# untitled_-.net
KiCad netlist of a schematic drawn in EAGLE
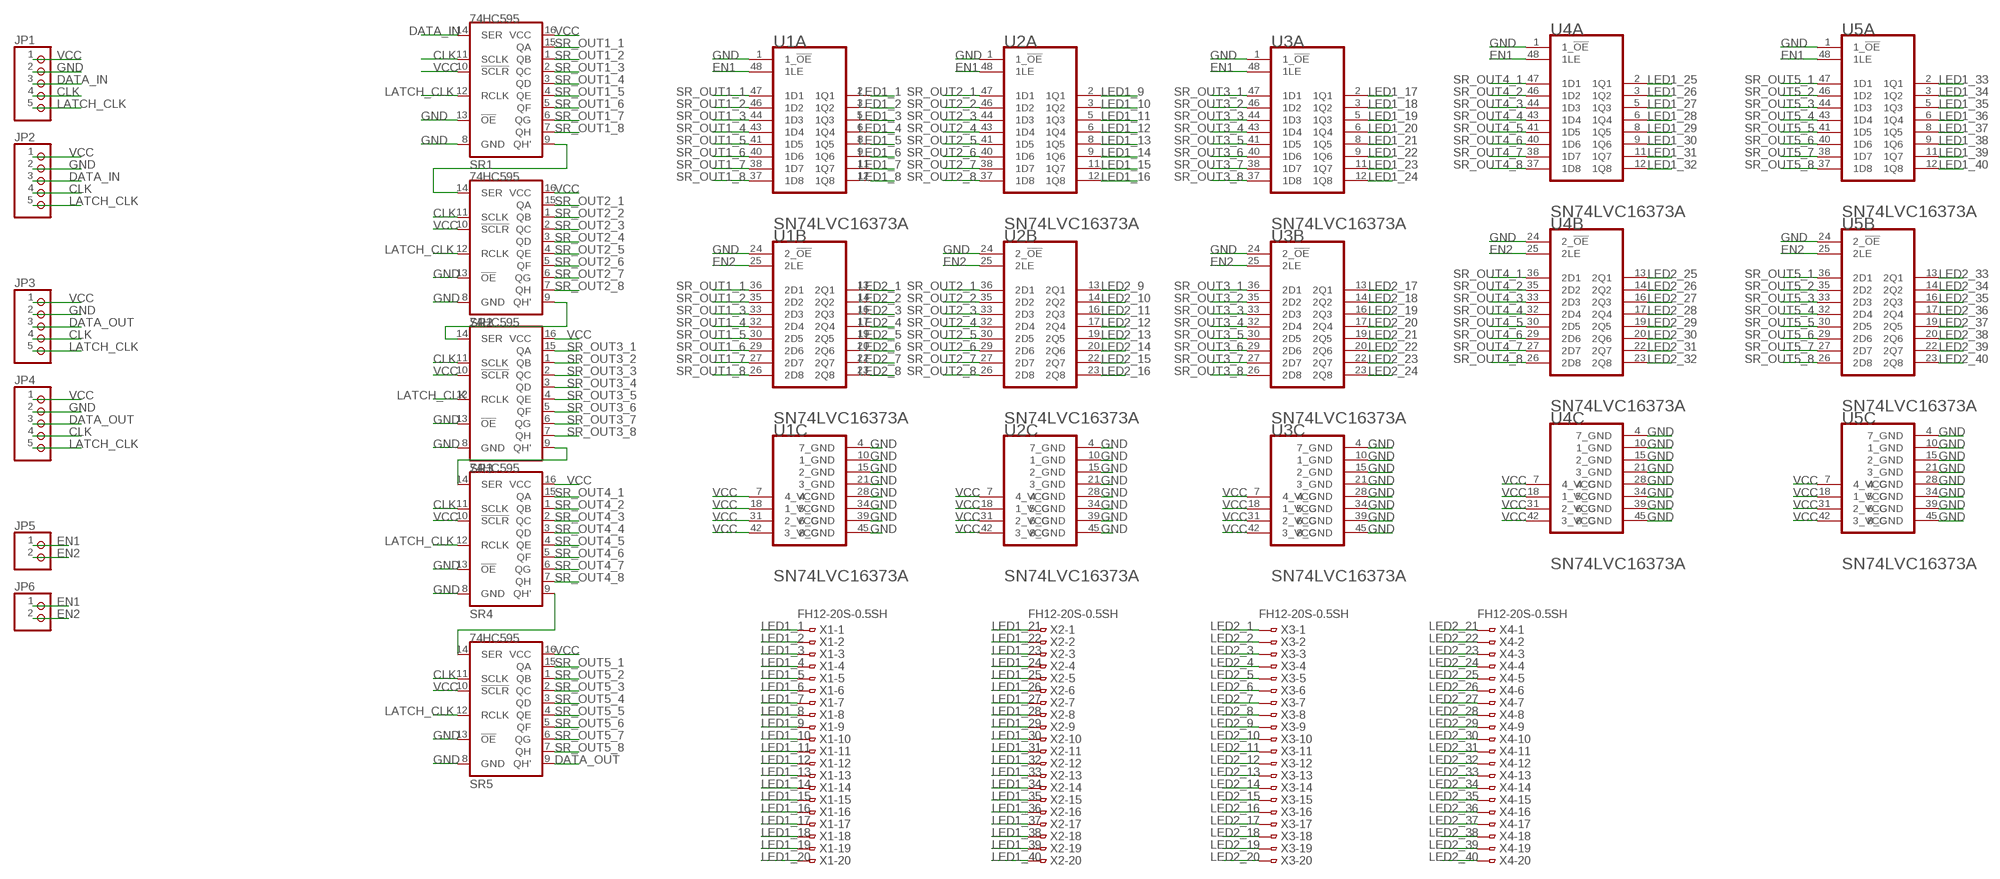
[diagram p0: schematic, sheet 1]

(export (version "E")
  (design (tool "Eeschema 10.0.6"))
  (components
    (comp (ref "JP1")
      (value "PINHD-1X5")
      (footprint "eagle-import:1X05")
      (libsource (lib "eagle-import") (part "PINHD-1X5"))
    )
    (comp (ref "JP2")
      (value "PINHD-1X5")
      (footprint "eagle-import:1X05")
      (libsource (lib "eagle-import") (part "PINHD-1X5"))
    )
    (comp (ref "JP3")
      (value "PINHD-1X5")
      (footprint "eagle-import:1X05")
      (libsource (lib "eagle-import") (part "PINHD-1X5"))
    )
    (comp (ref "JP4")
      (value "PINHD-1X5")
      (footprint "eagle-import:1X05")
      (libsource (lib "eagle-import") (part "PINHD-1X5"))
    )
    (comp (ref "JP5")
      (value "PINHD-1X2")
      (footprint "eagle-import:1X02")
      (libsource (lib "eagle-import") (part "PINHD-1X2"))
    )
    (comp (ref "JP6")
      (value "PINHD-1X2")
      (footprint "eagle-import:1X02")
      (libsource (lib "eagle-import") (part "PINHD-1X2"))
    )
    (comp (ref "SR1")
      (value "74HC595")
      (footprint "eagle-import:SO16")
      (fields (field (name "MF") "Nexperia"))
      (libsource (lib "eagle-import") (part "74HC595"))
    )
    (comp (ref "SR2")
      (value "74HC595")
      (footprint "eagle-import:SO16")
      (fields (field (name "MF") "Nexperia"))
      (libsource (lib "eagle-import") (part "74HC595"))
    )
    (comp (ref "SR3")
      (value "74HC595")
      (footprint "eagle-import:SO16")
      (fields (field (name "MF") "Nexperia"))
      (libsource (lib "eagle-import") (part "74HC595"))
    )
    (comp (ref "SR4")
      (value "74HC595")
      (footprint "eagle-import:SO16")
      (fields (field (name "MF") "Nexperia"))
      (libsource (lib "eagle-import") (part "74HC595"))
    )
    (comp (ref "SR5")
      (value "74HC595")
      (footprint "eagle-import:SO16")
      (fields (field (name "MF") "Nexperia"))
      (libsource (lib "eagle-import") (part "74HC595"))
    )
    (comp (ref "U1")
      (value "TEXAS_INSTRUMENTS_SN74LVC16373ATEXAS_INSTRUMENTS_SN74LVC16373A_0_2")
      (footprint "eagle-import:TEXAS_INSTRUMENTS_SN74LVC16373A_2")
      (fields (field (name "MF") "Texas Instruments") (field (name "MPN") "SN74LVC16373A"))
      (libsource (lib "eagle-import") (part "TEXAS_INSTRUMENTS_SN74LVC16373ATEXAS_INSTRUMENTS_SN74LVC16373A_0_2"))
    )
    (comp (ref "U2")
      (value "TEXAS_INSTRUMENTS_SN74LVC16373ATEXAS_INSTRUMENTS_SN74LVC16373A_0_2")
      (footprint "eagle-import:TEXAS_INSTRUMENTS_SN74LVC16373A_2")
      (fields (field (name "MF") "Texas Instruments") (field (name "MPN") "SN74LVC16373A"))
      (libsource (lib "eagle-import") (part "TEXAS_INSTRUMENTS_SN74LVC16373ATEXAS_INSTRUMENTS_SN74LVC16373A_0_2"))
    )
    (comp (ref "U3")
      (value "TEXAS_INSTRUMENTS_SN74LVC16373ATEXAS_INSTRUMENTS_SN74LVC16373A_0_2")
      (footprint "eagle-import:TEXAS_INSTRUMENTS_SN74LVC16373A_2")
      (fields (field (name "MF") "Texas Instruments") (field (name "MPN") "SN74LVC16373A"))
      (libsource (lib "eagle-import") (part "TEXAS_INSTRUMENTS_SN74LVC16373ATEXAS_INSTRUMENTS_SN74LVC16373A_0_2"))
    )
    (comp (ref "U4")
      (value "TEXAS_INSTRUMENTS_SN74LVC16373ATEXAS_INSTRUMENTS_SN74LVC16373A_0_2")
      (footprint "eagle-import:TEXAS_INSTRUMENTS_SN74LVC16373A_2")
      (fields (field (name "MF") "Texas Instruments") (field (name "MPN") "SN74LVC16373A"))
      (libsource (lib "eagle-import") (part "TEXAS_INSTRUMENTS_SN74LVC16373ATEXAS_INSTRUMENTS_SN74LVC16373A_0_2"))
    )
    (comp (ref "U5")
      (value "TEXAS_INSTRUMENTS_SN74LVC16373ATEXAS_INSTRUMENTS_SN74LVC16373A_0_2")
      (footprint "eagle-import:TEXAS_INSTRUMENTS_SN74LVC16373A_2")
      (fields (field (name "MF") "Texas Instruments") (field (name "MPN") "SN74LVC16373A"))
      (libsource (lib "eagle-import") (part "TEXAS_INSTRUMENTS_SN74LVC16373ATEXAS_INSTRUMENTS_SN74LVC16373A_0_2"))
    )
    (comp (ref "X1")
      (value "FH12-20S-0.5SH")
      (footprint "eagle-import:FH12-20S-0.5SH")
      (fields (field (name "MPN") "FH12-20S-0.5SH(55)"))
      (libsource (lib "eagle-import") (part "FH12-20S-0.5SH"))
    )
    (comp (ref "X2")
      (value "FH12-20S-0.5SH")
      (footprint "eagle-import:FH12-20S-0.5SH")
      (fields (field (name "MPN") "FH12-20S-0.5SH(55)"))
      (libsource (lib "eagle-import") (part "FH12-20S-0.5SH"))
    )
    (comp (ref "X3")
      (value "FH12-20S-0.5SH")
      (footprint "eagle-import:FH12-20S-0.5SH")
      (fields (field (name "MPN") "FH12-20S-0.5SH(55)"))
      (libsource (lib "eagle-import") (part "FH12-20S-0.5SH"))
    )
    (comp (ref "X4")
      (value "FH12-20S-0.5SH")
      (footprint "eagle-import:FH12-20S-0.5SH")
      (fields (field (name "MPN") "FH12-20S-0.5SH(55)"))
      (libsource (lib "eagle-import") (part "FH12-20S-0.5SH"))
    )
  )
  (nets
    (net (code "1") (name "/CLK") (class "Default")
      (node (ref "JP1") (pin "4") (pinfunction "4_4") (pintype "passive"))
      (node (ref "JP2") (pin "4") (pinfunction "4_4") (pintype "passive"))
      (node (ref "JP3") (pin "4") (pinfunction "4_4") (pintype "passive"))
      (node (ref "JP4") (pin "4") (pinfunction "4_4") (pintype "passive"))
      (node (ref "SR1") (pin "11") (pinfunction "SCLK_11") (pintype "input"))
      (node (ref "SR2") (pin "11") (pinfunction "SCLK_11") (pintype "input"))
      (node (ref "SR3") (pin "11") (pinfunction "SCLK_11") (pintype "input"))
      (node (ref "SR4") (pin "11") (pinfunction "SCLK_11") (pintype "input"))
      (node (ref "SR5") (pin "11") (pinfunction "SCLK_11") (pintype "input"))
    )
    (net (code "2") (name "/DATA_IN") (class "Default")
      (node (ref "JP1") (pin "3") (pinfunction "3_3") (pintype "passive"))
      (node (ref "JP2") (pin "3") (pinfunction "3_3") (pintype "passive"))
      (node (ref "SR1") (pin "14") (pinfunction "SER_14") (pintype "input"))
    )
    (net (code "3") (name "/DATA_OUT") (class "Default")
      (node (ref "JP3") (pin "3") (pinfunction "3_3") (pintype "passive"))
      (node (ref "JP4") (pin "3") (pinfunction "3_3") (pintype "passive"))
      (node (ref "SR5") (pin "9") (pinfunction "QH'_9") (pintype "tri_state"))
    )
    (net (code "4") (name "/EN1") (class "Default")
      (node (ref "JP5") (pin "1") (pinfunction "1_1") (pintype "passive"))
      (node (ref "JP6") (pin "1") (pinfunction "1_1") (pintype "passive"))
      (node (ref "U1") (pin "48") (pinfunction "1LE_48") (pintype "input"))
      (node (ref "U2") (pin "48") (pinfunction "1LE_48") (pintype "input"))
      (node (ref "U3") (pin "48") (pinfunction "1LE_48") (pintype "input"))
      (node (ref "U4") (pin "48") (pinfunction "1LE_48") (pintype "input"))
      (node (ref "U5") (pin "48") (pinfunction "1LE_48") (pintype "input"))
    )
    (net (code "5") (name "/EN2") (class "Default")
      (node (ref "JP5") (pin "2") (pinfunction "2_2") (pintype "passive"))
      (node (ref "JP6") (pin "2") (pinfunction "2_2") (pintype "passive"))
      (node (ref "U1") (pin "25") (pinfunction "2LE_25") (pintype "input"))
      (node (ref "U2") (pin "25") (pinfunction "2LE_25") (pintype "input"))
      (node (ref "U3") (pin "25") (pinfunction "2LE_25") (pintype "input"))
      (node (ref "U4") (pin "25") (pinfunction "2LE_25") (pintype "input"))
      (node (ref "U5") (pin "25") (pinfunction "2LE_25") (pintype "input"))
    )
    (net (code "6") (name "/GND") (class "Default")
      (node (ref "JP1") (pin "2") (pinfunction "2_2") (pintype "passive"))
      (node (ref "JP2") (pin "2") (pinfunction "2_2") (pintype "passive"))
      (node (ref "JP3") (pin "2") (pinfunction "2_2") (pintype "passive"))
      (node (ref "JP4") (pin "2") (pinfunction "2_2") (pintype "passive"))
      (node (ref "SR1") (pin "13") (pinfunction "~{OE}_13") (pintype "input"))
      (node (ref "SR1") (pin "8") (pinfunction "GND_8") (pintype "power_in"))
      (node (ref "SR2") (pin "13") (pinfunction "~{OE}_13") (pintype "input"))
      (node (ref "SR2") (pin "8") (pinfunction "GND_8") (pintype "power_in"))
      (node (ref "SR3") (pin "13") (pinfunction "~{OE}_13") (pintype "input"))
      (node (ref "SR3") (pin "8") (pinfunction "GND_8") (pintype "power_in"))
      (node (ref "SR4") (pin "13") (pinfunction "~{OE}_13") (pintype "input"))
      (node (ref "SR4") (pin "8") (pinfunction "GND_8") (pintype "power_in"))
      (node (ref "SR5") (pin "13") (pinfunction "~{OE}_13") (pintype "input"))
      (node (ref "SR5") (pin "8") (pinfunction "GND_8") (pintype "power_in"))
      (node (ref "U1") (pin "1") (pinfunction "1_~{OE}_1") (pintype "input"))
      (node (ref "U1") (pin "10") (pinfunction "1_GND_10") (pintype "power_in"))
      (node (ref "U1") (pin "15") (pinfunction "2_GND_15") (pintype "power_in"))
      (node (ref "U1") (pin "21") (pinfunction "3_GND_21") (pintype "power_in"))
      (node (ref "U1") (pin "24") (pinfunction "2_~{OE}_24") (pintype "input"))
      (node (ref "U1") (pin "28") (pinfunction "4_GND_28") (pintype "power_in"))
      (node (ref "U1") (pin "34") (pinfunction "5_GND_34") (pintype "power_in"))
      (node (ref "U1") (pin "39") (pinfunction "6_GND_39") (pintype "power_in"))
      (node (ref "U1") (pin "4") (pinfunction "7_GND_4") (pintype "power_in"))
      (node (ref "U1") (pin "45") (pinfunction "8_GND_45") (pintype "power_in"))
      (node (ref "U2") (pin "1") (pinfunction "1_~{OE}_1") (pintype "input"))
      (node (ref "U2") (pin "10") (pinfunction "1_GND_10") (pintype "power_in"))
      (node (ref "U2") (pin "15") (pinfunction "2_GND_15") (pintype "power_in"))
      (node (ref "U2") (pin "21") (pinfunction "3_GND_21") (pintype "power_in"))
      (node (ref "U2") (pin "24") (pinfunction "2_~{OE}_24") (pintype "input"))
      (node (ref "U2") (pin "28") (pinfunction "4_GND_28") (pintype "power_in"))
      (node (ref "U2") (pin "34") (pinfunction "5_GND_34") (pintype "power_in"))
      (node (ref "U2") (pin "39") (pinfunction "6_GND_39") (pintype "power_in"))
      (node (ref "U2") (pin "4") (pinfunction "7_GND_4") (pintype "power_in"))
      (node (ref "U2") (pin "45") (pinfunction "8_GND_45") (pintype "power_in"))
      (node (ref "U3") (pin "1") (pinfunction "1_~{OE}_1") (pintype "input"))
      (node (ref "U3") (pin "10") (pinfunction "1_GND_10") (pintype "power_in"))
      (node (ref "U3") (pin "15") (pinfunction "2_GND_15") (pintype "power_in"))
      (node (ref "U3") (pin "21") (pinfunction "3_GND_21") (pintype "power_in"))
      (node (ref "U3") (pin "24") (pinfunction "2_~{OE}_24") (pintype "input"))
      (node (ref "U3") (pin "28") (pinfunction "4_GND_28") (pintype "power_in"))
      (node (ref "U3") (pin "34") (pinfunction "5_GND_34") (pintype "power_in"))
      (node (ref "U3") (pin "39") (pinfunction "6_GND_39") (pintype "power_in"))
      (node (ref "U3") (pin "4") (pinfunction "7_GND_4") (pintype "power_in"))
      (node (ref "U3") (pin "45") (pinfunction "8_GND_45") (pintype "power_in"))
      (node (ref "U4") (pin "1") (pinfunction "1_~{OE}_1") (pintype "input"))
      (node (ref "U4") (pin "10") (pinfunction "1_GND_10") (pintype "power_in"))
      (node (ref "U4") (pin "15") (pinfunction "2_GND_15") (pintype "power_in"))
      (node (ref "U4") (pin "21") (pinfunction "3_GND_21") (pintype "power_in"))
      (node (ref "U4") (pin "24") (pinfunction "2_~{OE}_24") (pintype "input"))
      (node (ref "U4") (pin "28") (pinfunction "4_GND_28") (pintype "power_in"))
      (node (ref "U4") (pin "34") (pinfunction "5_GND_34") (pintype "power_in"))
      (node (ref "U4") (pin "39") (pinfunction "6_GND_39") (pintype "power_in"))
      (node (ref "U4") (pin "4") (pinfunction "7_GND_4") (pintype "power_in"))
      (node (ref "U4") (pin "45") (pinfunction "8_GND_45") (pintype "power_in"))
      (node (ref "U5") (pin "1") (pinfunction "1_~{OE}_1") (pintype "input"))
      (node (ref "U5") (pin "10") (pinfunction "1_GND_10") (pintype "power_in"))
      (node (ref "U5") (pin "15") (pinfunction "2_GND_15") (pintype "power_in"))
      (node (ref "U5") (pin "21") (pinfunction "3_GND_21") (pintype "power_in"))
      (node (ref "U5") (pin "24") (pinfunction "2_~{OE}_24") (pintype "input"))
      (node (ref "U5") (pin "28") (pinfunction "4_GND_28") (pintype "power_in"))
      (node (ref "U5") (pin "34") (pinfunction "5_GND_34") (pintype "power_in"))
      (node (ref "U5") (pin "39") (pinfunction "6_GND_39") (pintype "power_in"))
      (node (ref "U5") (pin "4") (pinfunction "7_GND_4") (pintype "power_in"))
      (node (ref "U5") (pin "45") (pinfunction "8_GND_45") (pintype "power_in"))
    )
    (net (code "7") (name "/LATCH_CLK") (class "Default")
      (node (ref "JP1") (pin "5") (pinfunction "5_5") (pintype "passive"))
      (node (ref "JP2") (pin "5") (pinfunction "5_5") (pintype "passive"))
      (node (ref "JP3") (pin "5") (pinfunction "5_5") (pintype "passive"))
      (node (ref "JP4") (pin "5") (pinfunction "5_5") (pintype "passive"))
      (node (ref "SR1") (pin "12") (pinfunction "RCLK_12") (pintype "input"))
      (node (ref "SR2") (pin "12") (pinfunction "RCLK_12") (pintype "input"))
      (node (ref "SR3") (pin "12") (pinfunction "RCLK_12") (pintype "input"))
      (node (ref "SR4") (pin "12") (pinfunction "RCLK_12") (pintype "input"))
      (node (ref "SR5") (pin "12") (pinfunction "RCLK_12") (pintype "input"))
    )
    (net (code "8") (name "/LED1_1") (class "Default")
      (node (ref "U1") (pin "2") (pinfunction "1Q1_2") (pintype "tri_state"))
      (node (ref "X1") (pin "1") (pinfunction "1_1") (pintype "passive"))
    )
    (net (code "9") (name "/LED1_2") (class "Default")
      (node (ref "U1") (pin "3") (pinfunction "1Q2_3") (pintype "tri_state"))
      (node (ref "X1") (pin "2") (pinfunction "1_2") (pintype "passive"))
    )
    (net (code "10") (name "/LED1_3") (class "Default")
      (node (ref "U1") (pin "5") (pinfunction "1Q3_5") (pintype "tri_state"))
      (node (ref "X1") (pin "3") (pinfunction "1_3") (pintype "passive"))
    )
    (net (code "11") (name "/LED1_4") (class "Default")
      (node (ref "U1") (pin "6") (pinfunction "1Q4_6") (pintype "tri_state"))
      (node (ref "X1") (pin "4") (pinfunction "1_4") (pintype "passive"))
    )
    (net (code "12") (name "/LED1_5") (class "Default")
      (node (ref "U1") (pin "8") (pinfunction "1Q5_8") (pintype "tri_state"))
      (node (ref "X1") (pin "5") (pinfunction "1_5") (pintype "passive"))
    )
    (net (code "13") (name "/LED1_6") (class "Default")
      (node (ref "U1") (pin "9") (pinfunction "1Q6_9") (pintype "tri_state"))
      (node (ref "X1") (pin "6") (pinfunction "1_6") (pintype "passive"))
    )
    (net (code "14") (name "/LED1_7") (class "Default")
      (node (ref "U1") (pin "11") (pinfunction "1Q7_11") (pintype "tri_state"))
      (node (ref "X1") (pin "7") (pinfunction "1_7") (pintype "passive"))
    )
    (net (code "15") (name "/LED1_8") (class "Default")
      (node (ref "U1") (pin "12") (pinfunction "1Q8_12") (pintype "tri_state"))
      (node (ref "X1") (pin "8") (pinfunction "1_8") (pintype "passive"))
    )
    (net (code "16") (name "/LED1_9") (class "Default")
      (node (ref "U2") (pin "2") (pinfunction "1Q1_2") (pintype "tri_state"))
      (node (ref "X1") (pin "9") (pinfunction "1_9") (pintype "passive"))
    )
    (net (code "17") (name "/LED1_10") (class "Default")
      (node (ref "U2") (pin "3") (pinfunction "1Q2_3") (pintype "tri_state"))
      (node (ref "X1") (pin "10") (pinfunction "1_10") (pintype "passive"))
    )
    (net (code "18") (name "/LED1_11") (class "Default")
      (node (ref "U2") (pin "5") (pinfunction "1Q3_5") (pintype "tri_state"))
      (node (ref "X1") (pin "11") (pinfunction "1_11") (pintype "passive"))
    )
    (net (code "19") (name "/LED1_12") (class "Default")
      (node (ref "U2") (pin "6") (pinfunction "1Q4_6") (pintype "tri_state"))
      (node (ref "X1") (pin "12") (pinfunction "1_12") (pintype "passive"))
    )
    (net (code "20") (name "/LED1_13") (class "Default")
      (node (ref "U2") (pin "8") (pinfunction "1Q5_8") (pintype "tri_state"))
      (node (ref "X1") (pin "13") (pinfunction "1_13") (pintype "passive"))
    )
    (net (code "21") (name "/LED1_14") (class "Default")
      (node (ref "U2") (pin "9") (pinfunction "1Q6_9") (pintype "tri_state"))
      (node (ref "X1") (pin "14") (pinfunction "1_14") (pintype "passive"))
    )
    (net (code "22") (name "/LED1_15") (class "Default")
      (node (ref "U2") (pin "11") (pinfunction "1Q7_11") (pintype "tri_state"))
      (node (ref "X1") (pin "15") (pinfunction "1_15") (pintype "passive"))
    )
    (net (code "23") (name "/LED1_16") (class "Default")
      (node (ref "U2") (pin "12") (pinfunction "1Q8_12") (pintype "tri_state"))
      (node (ref "X1") (pin "16") (pinfunction "1_16") (pintype "passive"))
    )
    (net (code "24") (name "/LED1_17") (class "Default")
      (node (ref "U3") (pin "2") (pinfunction "1Q1_2") (pintype "tri_state"))
      (node (ref "X1") (pin "17") (pinfunction "1_17") (pintype "passive"))
    )
    (net (code "25") (name "/LED1_18") (class "Default")
      (node (ref "U3") (pin "3") (pinfunction "1Q2_3") (pintype "tri_state"))
      (node (ref "X1") (pin "18") (pinfunction "1_18") (pintype "passive"))
    )
    (net (code "26") (name "/LED1_19") (class "Default")
      (node (ref "U3") (pin "5") (pinfunction "1Q3_5") (pintype "tri_state"))
      (node (ref "X1") (pin "19") (pinfunction "1_19") (pintype "passive"))
    )
    (net (code "27") (name "/LED1_20") (class "Default")
      (node (ref "U3") (pin "6") (pinfunction "1Q4_6") (pintype "tri_state"))
      (node (ref "X1") (pin "20") (pinfunction "1_20") (pintype "passive"))
    )
    (net (code "28") (name "/LED1_21") (class "Default")
      (node (ref "U3") (pin "8") (pinfunction "1Q5_8") (pintype "tri_state"))
      (node (ref "X2") (pin "1") (pinfunction "1_1") (pintype "passive"))
    )
    (net (code "29") (name "/LED1_22") (class "Default")
      (node (ref "U3") (pin "9") (pinfunction "1Q6_9") (pintype "tri_state"))
      (node (ref "X2") (pin "2") (pinfunction "1_2") (pintype "passive"))
    )
    (net (code "30") (name "/LED1_23") (class "Default")
      (node (ref "U3") (pin "11") (pinfunction "1Q7_11") (pintype "tri_state"))
      (node (ref "X2") (pin "3") (pinfunction "1_3") (pintype "passive"))
    )
    (net (code "31") (name "/LED1_24") (class "Default")
      (node (ref "U3") (pin "12") (pinfunction "1Q8_12") (pintype "tri_state"))
      (node (ref "X2") (pin "4") (pinfunction "1_4") (pintype "passive"))
    )
    (net (code "32") (name "/LED1_25") (class "Default")
      (node (ref "U4") (pin "2") (pinfunction "1Q1_2") (pintype "tri_state"))
      (node (ref "X2") (pin "5") (pinfunction "1_5") (pintype "passive"))
    )
    (net (code "33") (name "/LED1_26") (class "Default")
      (node (ref "U4") (pin "3") (pinfunction "1Q2_3") (pintype "tri_state"))
      (node (ref "X2") (pin "6") (pinfunction "1_6") (pintype "passive"))
    )
    (net (code "34") (name "/LED1_27") (class "Default")
      (node (ref "U4") (pin "5") (pinfunction "1Q3_5") (pintype "tri_state"))
      (node (ref "X2") (pin "7") (pinfunction "1_7") (pintype "passive"))
    )
    (net (code "35") (name "/LED1_28") (class "Default")
      (node (ref "U4") (pin "6") (pinfunction "1Q4_6") (pintype "tri_state"))
      (node (ref "X2") (pin "8") (pinfunction "1_8") (pintype "passive"))
    )
    (net (code "36") (name "/LED1_29") (class "Default")
      (node (ref "U4") (pin "8") (pinfunction "1Q5_8") (pintype "tri_state"))
      (node (ref "X2") (pin "9") (pinfunction "1_9") (pintype "passive"))
    )
    (net (code "37") (name "/LED1_30") (class "Default")
      (node (ref "U4") (pin "9") (pinfunction "1Q6_9") (pintype "tri_state"))
      (node (ref "X2") (pin "10") (pinfunction "1_10") (pintype "passive"))
    )
    (net (code "38") (name "/LED1_31") (class "Default")
      (node (ref "U4") (pin "11") (pinfunction "1Q7_11") (pintype "tri_state"))
      (node (ref "X2") (pin "11") (pinfunction "1_11") (pintype "passive"))
    )
    (net (code "39") (name "/LED1_32") (class "Default")
      (node (ref "U4") (pin "12") (pinfunction "1Q8_12") (pintype "tri_state"))
      (node (ref "X2") (pin "12") (pinfunction "1_12") (pintype "passive"))
    )
    (net (code "40") (name "/LED1_33") (class "Default")
      (node (ref "U5") (pin "2") (pinfunction "1Q1_2") (pintype "tri_state"))
      (node (ref "X2") (pin "13") (pinfunction "1_13") (pintype "passive"))
    )
    (net (code "41") (name "/LED1_34") (class "Default")
      (node (ref "U5") (pin "3") (pinfunction "1Q2_3") (pintype "tri_state"))
      (node (ref "X2") (pin "14") (pinfunction "1_14") (pintype "passive"))
    )
    (net (code "42") (name "/LED1_35") (class "Default")
      (node (ref "U5") (pin "5") (pinfunction "1Q3_5") (pintype "tri_state"))
      (node (ref "X2") (pin "15") (pinfunction "1_15") (pintype "passive"))
    )
    (net (code "43") (name "/LED1_36") (class "Default")
      (node (ref "U5") (pin "6") (pinfunction "1Q4_6") (pintype "tri_state"))
      (node (ref "X2") (pin "16") (pinfunction "1_16") (pintype "passive"))
    )
    (net (code "44") (name "/LED1_37") (class "Default")
      (node (ref "U5") (pin "8") (pinfunction "1Q5_8") (pintype "tri_state"))
      (node (ref "X2") (pin "17") (pinfunction "1_17") (pintype "passive"))
    )
    (net (code "45") (name "/LED1_38") (class "Default")
      (node (ref "U5") (pin "9") (pinfunction "1Q6_9") (pintype "tri_state"))
      (node (ref "X2") (pin "18") (pinfunction "1_18") (pintype "passive"))
    )
    (net (code "46") (name "/LED1_39") (class "Default")
      (node (ref "U5") (pin "11") (pinfunction "1Q7_11") (pintype "tri_state"))
      (node (ref "X2") (pin "19") (pinfunction "1_19") (pintype "passive"))
    )
    (net (code "47") (name "/LED1_40") (class "Default")
      (node (ref "U5") (pin "12") (pinfunction "1Q8_12") (pintype "tri_state"))
      (node (ref "X2") (pin "20") (pinfunction "1_20") (pintype "passive"))
    )
    (net (code "48") (name "/LED2_1") (class "Default")
      (node (ref "U1") (pin "13") (pinfunction "2Q1_13") (pintype "tri_state"))
      (node (ref "X3") (pin "1") (pinfunction "1_1") (pintype "passive"))
    )
    (net (code "49") (name "/LED2_2") (class "Default")
      (node (ref "U1") (pin "14") (pinfunction "2Q2_14") (pintype "tri_state"))
      (node (ref "X3") (pin "2") (pinfunction "1_2") (pintype "passive"))
    )
    (net (code "50") (name "/LED2_3") (class "Default")
      (node (ref "U1") (pin "16") (pinfunction "2Q3_16") (pintype "tri_state"))
      (node (ref "X3") (pin "3") (pinfunction "1_3") (pintype "passive"))
    )
    (net (code "51") (name "/LED2_4") (class "Default")
      (node (ref "U1") (pin "17") (pinfunction "2Q4_17") (pintype "tri_state"))
      (node (ref "X3") (pin "4") (pinfunction "1_4") (pintype "passive"))
    )
    (net (code "52") (name "/LED2_5") (class "Default")
      (node (ref "U1") (pin "19") (pinfunction "2Q5_19") (pintype "tri_state"))
      (node (ref "X3") (pin "5") (pinfunction "1_5") (pintype "passive"))
    )
    (net (code "53") (name "/LED2_6") (class "Default")
      (node (ref "U1") (pin "20") (pinfunction "2Q6_20") (pintype "tri_state"))
      (node (ref "X3") (pin "6") (pinfunction "1_6") (pintype "passive"))
    )
    (net (code "54") (name "/LED2_7") (class "Default")
      (node (ref "U1") (pin "22") (pinfunction "2Q7_22") (pintype "tri_state"))
      (node (ref "X3") (pin "7") (pinfunction "1_7") (pintype "passive"))
    )
    (net (code "55") (name "/LED2_8") (class "Default")
      (node (ref "U1") (pin "23") (pinfunction "2Q8_23") (pintype "tri_state"))
      (node (ref "X3") (pin "8") (pinfunction "1_8") (pintype "passive"))
    )
    (net (code "56") (name "/LED2_9") (class "Default")
      (node (ref "U2") (pin "13") (pinfunction "2Q1_13") (pintype "tri_state"))
      (node (ref "X3") (pin "9") (pinfunction "1_9") (pintype "passive"))
    )
    (net (code "57") (name "/LED2_10") (class "Default")
      (node (ref "U2") (pin "14") (pinfunction "2Q2_14") (pintype "tri_state"))
      (node (ref "X3") (pin "10") (pinfunction "1_10") (pintype "passive"))
    )
    (net (code "58") (name "/LED2_11") (class "Default")
      (node (ref "U2") (pin "16") (pinfunction "2Q3_16") (pintype "tri_state"))
      (node (ref "X3") (pin "11") (pinfunction "1_11") (pintype "passive"))
    )
    (net (code "59") (name "/LED2_12") (class "Default")
      (node (ref "U2") (pin "17") (pinfunction "2Q4_17") (pintype "tri_state"))
      (node (ref "X3") (pin "12") (pinfunction "1_12") (pintype "passive"))
    )
    (net (code "60") (name "/LED2_13") (class "Default")
      (node (ref "U2") (pin "19") (pinfunction "2Q5_19") (pintype "tri_state"))
      (node (ref "X3") (pin "13") (pinfunction "1_13") (pintype "passive"))
    )
    (net (code "61") (name "/LED2_14") (class "Default")
      (node (ref "U2") (pin "20") (pinfunction "2Q6_20") (pintype "tri_state"))
      (node (ref "X3") (pin "14") (pinfunction "1_14") (pintype "passive"))
    )
    (net (code "62") (name "/LED2_15") (class "Default")
      (node (ref "U2") (pin "22") (pinfunction "2Q7_22") (pintype "tri_state"))
      (node (ref "X3") (pin "15") (pinfunction "1_15") (pintype "passive"))
    )
    (net (code "63") (name "/LED2_16") (class "Default")
      (node (ref "U2") (pin "23") (pinfunction "2Q8_23") (pintype "tri_state"))
      (node (ref "X3") (pin "16") (pinfunction "1_16") (pintype "passive"))
    )
    (net (code "64") (name "/LED2_17") (class "Default")
      (node (ref "U3") (pin "13") (pinfunction "2Q1_13") (pintype "tri_state"))
      (node (ref "X3") (pin "17") (pinfunction "1_17") (pintype "passive"))
    )
    (net (code "65") (name "/LED2_18") (class "Default")
      (node (ref "U3") (pin "14") (pinfunction "2Q2_14") (pintype "tri_state"))
      (node (ref "X3") (pin "18") (pinfunction "1_18") (pintype "passive"))
    )
    (net (code "66") (name "/LED2_19") (class "Default")
      (node (ref "U3") (pin "16") (pinfunction "2Q3_16") (pintype "tri_state"))
      (node (ref "X3") (pin "19") (pinfunction "1_19") (pintype "passive"))
    )
    (net (code "67") (name "/LED2_20") (class "Default")
      (node (ref "U3") (pin "17") (pinfunction "2Q4_17") (pintype "tri_state"))
      (node (ref "X3") (pin "20") (pinfunction "1_20") (pintype "passive"))
    )
    (net (code "68") (name "/LED2_21") (class "Default")
      (node (ref "U3") (pin "19") (pinfunction "2Q5_19") (pintype "tri_state"))
      (node (ref "X4") (pin "1") (pinfunction "1_1") (pintype "passive"))
    )
    (net (code "69") (name "/LED2_22") (class "Default")
      (node (ref "U3") (pin "20") (pinfunction "2Q6_20") (pintype "tri_state"))
      (node (ref "X4") (pin "2") (pinfunction "1_2") (pintype "passive"))
    )
    (net (code "70") (name "/LED2_23") (class "Default")
      (node (ref "U3") (pin "22") (pinfunction "2Q7_22") (pintype "tri_state"))
      (node (ref "X4") (pin "3") (pinfunction "1_3") (pintype "passive"))
    )
    (net (code "71") (name "/LED2_24") (class "Default")
      (node (ref "U3") (pin "23") (pinfunction "2Q8_23") (pintype "tri_state"))
      (node (ref "X4") (pin "4") (pinfunction "1_4") (pintype "passive"))
    )
    (net (code "72") (name "/LED2_25") (class "Default")
      (node (ref "U4") (pin "13") (pinfunction "2Q1_13") (pintype "tri_state"))
      (node (ref "X4") (pin "5") (pinfunction "1_5") (pintype "passive"))
    )
    (net (code "73") (name "/LED2_26") (class "Default")
      (node (ref "U4") (pin "14") (pinfunction "2Q2_14") (pintype "tri_state"))
      (node (ref "X4") (pin "6") (pinfunction "1_6") (pintype "passive"))
    )
    (net (code "74") (name "/LED2_27") (class "Default")
      (node (ref "U4") (pin "16") (pinfunction "2Q3_16") (pintype "tri_state"))
      (node (ref "X4") (pin "7") (pinfunction "1_7") (pintype "passive"))
    )
    (net (code "75") (name "/LED2_28") (class "Default")
      (node (ref "U4") (pin "17") (pinfunction "2Q4_17") (pintype "tri_state"))
      (node (ref "X4") (pin "8") (pinfunction "1_8") (pintype "passive"))
    )
    (net (code "76") (name "/LED2_29") (class "Default")
      (node (ref "U4") (pin "19") (pinfunction "2Q5_19") (pintype "tri_state"))
      (node (ref "X4") (pin "9") (pinfunction "1_9") (pintype "passive"))
    )
    (net (code "77") (name "/LED2_30") (class "Default")
      (node (ref "U4") (pin "20") (pinfunction "2Q6_20") (pintype "tri_state"))
      (node (ref "X4") (pin "10") (pinfunction "1_10") (pintype "passive"))
    )
    (net (code "78") (name "/LED2_31") (class "Default")
      (node (ref "U4") (pin "22") (pinfunction "2Q7_22") (pintype "tri_state"))
      (node (ref "X4") (pin "11") (pinfunction "1_11") (pintype "passive"))
    )
    (net (code "79") (name "/LED2_32") (class "Default")
      (node (ref "U4") (pin "23") (pinfunction "2Q8_23") (pintype "tri_state"))
      (node (ref "X4") (pin "12") (pinfunction "1_12") (pintype "passive"))
    )
    (net (code "80") (name "/LED2_33") (class "Default")
      (node (ref "U5") (pin "13") (pinfunction "2Q1_13") (pintype "tri_state"))
      (node (ref "X4") (pin "13") (pinfunction "1_13") (pintype "passive"))
    )
    (net (code "81") (name "/LED2_34") (class "Default")
      (node (ref "U5") (pin "14") (pinfunction "2Q2_14") (pintype "tri_state"))
      (node (ref "X4") (pin "14") (pinfunction "1_14") (pintype "passive"))
    )
    (net (code "82") (name "/LED2_35") (class "Default")
      (node (ref "U5") (pin "16") (pinfunction "2Q3_16") (pintype "tri_state"))
      (node (ref "X4") (pin "15") (pinfunction "1_15") (pintype "passive"))
    )
    (net (code "83") (name "/LED2_36") (class "Default")
      (node (ref "U5") (pin "17") (pinfunction "2Q4_17") (pintype "tri_state"))
      (node (ref "X4") (pin "16") (pinfunction "1_16") (pintype "passive"))
    )
    (net (code "84") (name "/LED2_37") (class "Default")
      (node (ref "U5") (pin "19") (pinfunction "2Q5_19") (pintype "tri_state"))
      (node (ref "X4") (pin "17") (pinfunction "1_17") (pintype "passive"))
    )
    (net (code "85") (name "/LED2_38") (class "Default")
      (node (ref "U5") (pin "20") (pinfunction "2Q6_20") (pintype "tri_state"))
      (node (ref "X4") (pin "18") (pinfunction "1_18") (pintype "passive"))
    )
    (net (code "86") (name "/LED2_39") (class "Default")
      (node (ref "U5") (pin "22") (pinfunction "2Q7_22") (pintype "tri_state"))
      (node (ref "X4") (pin "19") (pinfunction "1_19") (pintype "passive"))
    )
    (net (code "87") (name "/LED2_40") (class "Default")
      (node (ref "U5") (pin "23") (pinfunction "2Q8_23") (pintype "tri_state"))
      (node (ref "X4") (pin "20") (pinfunction "1_20") (pintype "passive"))
    )
    (net (code "88") (name "/SR_OUT1_1") (class "Default")
      (node (ref "SR1") (pin "15") (pinfunction "QA_15") (pintype "tri_state"))
      (node (ref "U1") (pin "36") (pinfunction "2D1_36") (pintype "input"))
      (node (ref "U1") (pin "47") (pinfunction "1D1_47") (pintype "input"))
    )
    (net (code "89") (name "/SR_OUT1_2") (class "Default")
      (node (ref "SR1") (pin "1") (pinfunction "QB_1") (pintype "tri_state"))
      (node (ref "U1") (pin "35") (pinfunction "2D2_35") (pintype "input"))
      (node (ref "U1") (pin "46") (pinfunction "1D2_46") (pintype "input"))
    )
    (net (code "90") (name "/SR_OUT1_3") (class "Default")
      (node (ref "SR1") (pin "2") (pinfunction "QC_2") (pintype "tri_state"))
      (node (ref "U1") (pin "33") (pinfunction "2D3_33") (pintype "input"))
      (node (ref "U1") (pin "44") (pinfunction "1D3_44") (pintype "input"))
    )
    (net (code "91") (name "/SR_OUT1_4") (class "Default")
      (node (ref "SR1") (pin "3") (pinfunction "QD_3") (pintype "tri_state"))
      (node (ref "U1") (pin "32") (pinfunction "2D4_32") (pintype "input"))
      (node (ref "U1") (pin "43") (pinfunction "1D4_43") (pintype "input"))
    )
    (net (code "92") (name "/SR_OUT1_5") (class "Default")
      (node (ref "SR1") (pin "4") (pinfunction "QE_4") (pintype "tri_state"))
      (node (ref "U1") (pin "30") (pinfunction "2D5_30") (pintype "input"))
      (node (ref "U1") (pin "41") (pinfunction "1D5_41") (pintype "input"))
    )
    (net (code "93") (name "/SR_OUT1_6") (class "Default")
      (node (ref "SR1") (pin "5") (pinfunction "QF_5") (pintype "tri_state"))
      (node (ref "U1") (pin "29") (pinfunction "2D6_29") (pintype "input"))
      (node (ref "U1") (pin "40") (pinfunction "1D6_40") (pintype "input"))
    )
    (net (code "94") (name "/SR_OUT1_7") (class "Default")
      (node (ref "SR1") (pin "6") (pinfunction "QG_6") (pintype "tri_state"))
      (node (ref "U1") (pin "27") (pinfunction "2D7_27") (pintype "input"))
      (node (ref "U1") (pin "38") (pinfunction "1D7_38") (pintype "input"))
    )
    (net (code "95") (name "/SR_OUT1_8") (class "Default")
      (node (ref "SR1") (pin "7") (pinfunction "QH_7") (pintype "tri_state"))
      (node (ref "U1") (pin "26") (pinfunction "2D8_26") (pintype "input"))
      (node (ref "U1") (pin "37") (pinfunction "1D8_37") (pintype "input"))
    )
    (net (code "96") (name "/SR_OUT2_1") (class "Default")
      (node (ref "SR2") (pin "15") (pinfunction "QA_15") (pintype "tri_state"))
      (node (ref "U2") (pin "36") (pinfunction "2D1_36") (pintype "input"))
      (node (ref "U2") (pin "47") (pinfunction "1D1_47") (pintype "input"))
    )
    (net (code "97") (name "/SR_OUT2_2") (class "Default")
      (node (ref "SR2") (pin "1") (pinfunction "QB_1") (pintype "tri_state"))
      (node (ref "U2") (pin "35") (pinfunction "2D2_35") (pintype "input"))
      (node (ref "U2") (pin "46") (pinfunction "1D2_46") (pintype "input"))
    )
    (net (code "98") (name "/SR_OUT2_3") (class "Default")
      (node (ref "SR2") (pin "2") (pinfunction "QC_2") (pintype "tri_state"))
      (node (ref "U2") (pin "33") (pinfunction "2D3_33") (pintype "input"))
      (node (ref "U2") (pin "44") (pinfunction "1D3_44") (pintype "input"))
    )
    (net (code "99") (name "/SR_OUT2_4") (class "Default")
      (node (ref "SR2") (pin "3") (pinfunction "QD_3") (pintype "tri_state"))
      (node (ref "U2") (pin "32") (pinfunction "2D4_32") (pintype "input"))
      (node (ref "U2") (pin "43") (pinfunction "1D4_43") (pintype "input"))
    )
    (net (code "100") (name "/SR_OUT2_5") (class "Default")
      (node (ref "SR2") (pin "4") (pinfunction "QE_4") (pintype "tri_state"))
      (node (ref "U2") (pin "30") (pinfunction "2D5_30") (pintype "input"))
      (node (ref "U2") (pin "41") (pinfunction "1D5_41") (pintype "input"))
    )
    (net (code "101") (name "/SR_OUT2_6") (class "Default")
      (node (ref "SR2") (pin "5") (pinfunction "QF_5") (pintype "tri_state"))
      (node (ref "U2") (pin "29") (pinfunction "2D6_29") (pintype "input"))
      (node (ref "U2") (pin "40") (pinfunction "1D6_40") (pintype "input"))
    )
    (net (code "102") (name "/SR_OUT2_7") (class "Default")
      (node (ref "SR2") (pin "6") (pinfunction "QG_6") (pintype "tri_state"))
      (node (ref "U2") (pin "27") (pinfunction "2D7_27") (pintype "input"))
      (node (ref "U2") (pin "38") (pinfunction "1D7_38") (pintype "input"))
    )
    (net (code "103") (name "/SR_OUT2_8") (class "Default")
      (node (ref "SR2") (pin "7") (pinfunction "QH_7") (pintype "tri_state"))
      (node (ref "U2") (pin "26") (pinfunction "2D8_26") (pintype "input"))
      (node (ref "U2") (pin "37") (pinfunction "1D8_37") (pintype "input"))
    )
    (net (code "104") (name "/SR_OUT3_1") (class "Default")
      (node (ref "SR3") (pin "15") (pinfunction "QA_15") (pintype "tri_state"))
      (node (ref "U3") (pin "36") (pinfunction "2D1_36") (pintype "input"))
      (node (ref "U3") (pin "47") (pinfunction "1D1_47") (pintype "input"))
    )
    (net (code "105") (name "/SR_OUT3_2") (class "Default")
      (node (ref "SR3") (pin "1") (pinfunction "QB_1") (pintype "tri_state"))
      (node (ref "U3") (pin "35") (pinfunction "2D2_35") (pintype "input"))
      (node (ref "U3") (pin "46") (pinfunction "1D2_46") (pintype "input"))
    )
    (net (code "106") (name "/SR_OUT3_3") (class "Default")
      (node (ref "SR3") (pin "2") (pinfunction "QC_2") (pintype "tri_state"))
      (node (ref "U3") (pin "33") (pinfunction "2D3_33") (pintype "input"))
      (node (ref "U3") (pin "44") (pinfunction "1D3_44") (pintype "input"))
    )
    (net (code "107") (name "/SR_OUT3_4") (class "Default")
      (node (ref "SR3") (pin "3") (pinfunction "QD_3") (pintype "tri_state"))
      (node (ref "U3") (pin "32") (pinfunction "2D4_32") (pintype "input"))
      (node (ref "U3") (pin "43") (pinfunction "1D4_43") (pintype "input"))
    )
    (net (code "108") (name "/SR_OUT3_5") (class "Default")
      (node (ref "SR3") (pin "4") (pinfunction "QE_4") (pintype "tri_state"))
      (node (ref "U3") (pin "30") (pinfunction "2D5_30") (pintype "input"))
      (node (ref "U3") (pin "41") (pinfunction "1D5_41") (pintype "input"))
    )
    (net (code "109") (name "/SR_OUT3_6") (class "Default")
      (node (ref "SR3") (pin "5") (pinfunction "QF_5") (pintype "tri_state"))
      (node (ref "U3") (pin "29") (pinfunction "2D6_29") (pintype "input"))
      (node (ref "U3") (pin "40") (pinfunction "1D6_40") (pintype "input"))
    )
    (net (code "110") (name "/SR_OUT3_7") (class "Default")
      (node (ref "SR3") (pin "6") (pinfunction "QG_6") (pintype "tri_state"))
      (node (ref "U3") (pin "27") (pinfunction "2D7_27") (pintype "input"))
      (node (ref "U3") (pin "38") (pinfunction "1D7_38") (pintype "input"))
    )
    (net (code "111") (name "/SR_OUT3_8") (class "Default")
      (node (ref "SR3") (pin "7") (pinfunction "QH_7") (pintype "tri_state"))
      (node (ref "U3") (pin "26") (pinfunction "2D8_26") (pintype "input"))
      (node (ref "U3") (pin "37") (pinfunction "1D8_37") (pintype "input"))
    )
    (net (code "112") (name "/SR_OUT4_1") (class "Default")
      (node (ref "SR4") (pin "15") (pinfunction "QA_15") (pintype "tri_state"))
      (node (ref "U4") (pin "36") (pinfunction "2D1_36") (pintype "input"))
      (node (ref "U4") (pin "47") (pinfunction "1D1_47") (pintype "input"))
    )
    (net (code "113") (name "/SR_OUT4_2") (class "Default")
      (node (ref "SR4") (pin "1") (pinfunction "QB_1") (pintype "tri_state"))
      (node (ref "U4") (pin "35") (pinfunction "2D2_35") (pintype "input"))
      (node (ref "U4") (pin "46") (pinfunction "1D2_46") (pintype "input"))
    )
    (net (code "114") (name "/SR_OUT4_3") (class "Default")
      (node (ref "SR4") (pin "2") (pinfunction "QC_2") (pintype "tri_state"))
      (node (ref "U4") (pin "33") (pinfunction "2D3_33") (pintype "input"))
      (node (ref "U4") (pin "44") (pinfunction "1D3_44") (pintype "input"))
    )
    (net (code "115") (name "/SR_OUT4_4") (class "Default")
      (node (ref "SR4") (pin "3") (pinfunction "QD_3") (pintype "tri_state"))
      (node (ref "U4") (pin "32") (pinfunction "2D4_32") (pintype "input"))
      (node (ref "U4") (pin "43") (pinfunction "1D4_43") (pintype "input"))
    )
    (net (code "116") (name "/SR_OUT4_5") (class "Default")
      (node (ref "SR4") (pin "4") (pinfunction "QE_4") (pintype "tri_state"))
      (node (ref "U4") (pin "30") (pinfunction "2D5_30") (pintype "input"))
      (node (ref "U4") (pin "41") (pinfunction "1D5_41") (pintype "input"))
    )
    (net (code "117") (name "/SR_OUT4_6") (class "Default")
      (node (ref "SR4") (pin "5") (pinfunction "QF_5") (pintype "tri_state"))
      (node (ref "U4") (pin "29") (pinfunction "2D6_29") (pintype "input"))
      (node (ref "U4") (pin "40") (pinfunction "1D6_40") (pintype "input"))
    )
    (net (code "118") (name "/SR_OUT4_7") (class "Default")
      (node (ref "SR4") (pin "6") (pinfunction "QG_6") (pintype "tri_state"))
      (node (ref "U4") (pin "27") (pinfunction "2D7_27") (pintype "input"))
      (node (ref "U4") (pin "38") (pinfunction "1D7_38") (pintype "input"))
    )
    (net (code "119") (name "/SR_OUT4_8") (class "Default")
      (node (ref "SR4") (pin "7") (pinfunction "QH_7") (pintype "tri_state"))
      (node (ref "U4") (pin "26") (pinfunction "2D8_26") (pintype "input"))
      (node (ref "U4") (pin "37") (pinfunction "1D8_37") (pintype "input"))
    )
    (net (code "120") (name "/SR_OUT5_1") (class "Default")
      (node (ref "SR5") (pin "15") (pinfunction "QA_15") (pintype "tri_state"))
      (node (ref "U5") (pin "36") (pinfunction "2D1_36") (pintype "input"))
      (node (ref "U5") (pin "47") (pinfunction "1D1_47") (pintype "input"))
    )
    (net (code "121") (name "/SR_OUT5_2") (class "Default")
      (node (ref "SR5") (pin "1") (pinfunction "QB_1") (pintype "tri_state"))
      (node (ref "U5") (pin "35") (pinfunction "2D2_35") (pintype "input"))
      (node (ref "U5") (pin "46") (pinfunction "1D2_46") (pintype "input"))
    )
    (net (code "122") (name "/SR_OUT5_3") (class "Default")
      (node (ref "SR5") (pin "2") (pinfunction "QC_2") (pintype "tri_state"))
      (node (ref "U5") (pin "33") (pinfunction "2D3_33") (pintype "input"))
      (node (ref "U5") (pin "44") (pinfunction "1D3_44") (pintype "input"))
    )
    (net (code "123") (name "/SR_OUT5_4") (class "Default")
      (node (ref "SR5") (pin "3") (pinfunction "QD_3") (pintype "tri_state"))
      (node (ref "U5") (pin "32") (pinfunction "2D4_32") (pintype "input"))
      (node (ref "U5") (pin "43") (pinfunction "1D4_43") (pintype "input"))
    )
    (net (code "124") (name "/SR_OUT5_5") (class "Default")
      (node (ref "SR5") (pin "4") (pinfunction "QE_4") (pintype "tri_state"))
      (node (ref "U5") (pin "30") (pinfunction "2D5_30") (pintype "input"))
      (node (ref "U5") (pin "41") (pinfunction "1D5_41") (pintype "input"))
    )
    (net (code "125") (name "/SR_OUT5_6") (class "Default")
      (node (ref "SR5") (pin "5") (pinfunction "QF_5") (pintype "tri_state"))
      (node (ref "U5") (pin "29") (pinfunction "2D6_29") (pintype "input"))
      (node (ref "U5") (pin "40") (pinfunction "1D6_40") (pintype "input"))
    )
    (net (code "126") (name "/SR_OUT5_7") (class "Default")
      (node (ref "SR5") (pin "6") (pinfunction "QG_6") (pintype "tri_state"))
      (node (ref "U5") (pin "27") (pinfunction "2D7_27") (pintype "input"))
      (node (ref "U5") (pin "38") (pinfunction "1D7_38") (pintype "input"))
    )
    (net (code "127") (name "/SR_OUT5_8") (class "Default")
      (node (ref "SR5") (pin "7") (pinfunction "QH_7") (pintype "tri_state"))
      (node (ref "U5") (pin "26") (pinfunction "2D8_26") (pintype "input"))
      (node (ref "U5") (pin "37") (pinfunction "1D8_37") (pintype "input"))
    )
    (net (code "128") (name "/VCC") (class "Default")
      (node (ref "JP1") (pin "1") (pinfunction "1_1") (pintype "passive"))
      (node (ref "JP2") (pin "1") (pinfunction "1_1") (pintype "passive"))
      (node (ref "JP3") (pin "1") (pinfunction "1_1") (pintype "passive"))
      (node (ref "JP4") (pin "1") (pinfunction "1_1") (pintype "passive"))
      (node (ref "SR1") (pin "10") (pinfunction "~{SCLR}_10") (pintype "input"))
      (node (ref "SR1") (pin "16") (pinfunction "VCC_16") (pintype "power_in"))
      (node (ref "SR2") (pin "10") (pinfunction "~{SCLR}_10") (pintype "input"))
      (node (ref "SR2") (pin "16") (pinfunction "VCC_16") (pintype "power_in"))
      (node (ref "SR3") (pin "10") (pinfunction "~{SCLR}_10") (pintype "input"))
      (node (ref "SR3") (pin "16") (pinfunction "VCC_16") (pintype "power_in"))
      (node (ref "SR4") (pin "10") (pinfunction "~{SCLR}_10") (pintype "input"))
      (node (ref "SR4") (pin "16") (pinfunction "VCC_16") (pintype "power_in"))
      (node (ref "SR5") (pin "10") (pinfunction "~{SCLR}_10") (pintype "input"))
      (node (ref "SR5") (pin "16") (pinfunction "VCC_16") (pintype "power_in"))
      (node (ref "U1") (pin "18") (pinfunction "1_VCC_18") (pintype "power_in"))
      (node (ref "U1") (pin "31") (pinfunction "2_VCC_31") (pintype "power_in"))
      (node (ref "U1") (pin "42") (pinfunction "3_VCC_42") (pintype "power_in"))
      (node (ref "U1") (pin "7") (pinfunction "4_VCC_7") (pintype "power_in"))
      (node (ref "U2") (pin "18") (pinfunction "1_VCC_18") (pintype "power_in"))
      (node (ref "U2") (pin "31") (pinfunction "2_VCC_31") (pintype "power_in"))
      (node (ref "U2") (pin "42") (pinfunction "3_VCC_42") (pintype "power_in"))
      (node (ref "U2") (pin "7") (pinfunction "4_VCC_7") (pintype "power_in"))
      (node (ref "U3") (pin "18") (pinfunction "1_VCC_18") (pintype "power_in"))
      (node (ref "U3") (pin "31") (pinfunction "2_VCC_31") (pintype "power_in"))
      (node (ref "U3") (pin "42") (pinfunction "3_VCC_42") (pintype "power_in"))
      (node (ref "U3") (pin "7") (pinfunction "4_VCC_7") (pintype "power_in"))
      (node (ref "U4") (pin "18") (pinfunction "1_VCC_18") (pintype "power_in"))
      (node (ref "U4") (pin "31") (pinfunction "2_VCC_31") (pintype "power_in"))
      (node (ref "U4") (pin "42") (pinfunction "3_VCC_42") (pintype "power_in"))
      (node (ref "U4") (pin "7") (pinfunction "4_VCC_7") (pintype "power_in"))
      (node (ref "U5") (pin "18") (pinfunction "1_VCC_18") (pintype "power_in"))
      (node (ref "U5") (pin "31") (pinfunction "2_VCC_31") (pintype "power_in"))
      (node (ref "U5") (pin "42") (pinfunction "3_VCC_42") (pintype "power_in"))
      (node (ref "U5") (pin "7") (pinfunction "4_VCC_7") (pintype "power_in"))
    )
    (net (code "129") (name "Net-(SR1-QH')") (class "Default")
      (node (ref "SR1") (pin "9") (pinfunction "QH'_9") (pintype "tri_state"))
      (node (ref "SR2") (pin "14") (pinfunction "SER_14") (pintype "input"))
    )
    (net (code "130") (name "Net-(SR2-QH')") (class "Default")
      (node (ref "SR2") (pin "9") (pinfunction "QH'_9") (pintype "tri_state"))
      (node (ref "SR3") (pin "14") (pinfunction "SER_14") (pintype "input"))
    )
    (net (code "131") (name "Net-(SR3-QH')") (class "Default")
      (node (ref "SR3") (pin "9") (pinfunction "QH'_9") (pintype "tri_state"))
      (node (ref "SR4") (pin "14") (pinfunction "SER_14") (pintype "input"))
    )
    (net (code "132") (name "Net-(SR4-QH')") (class "Default")
      (node (ref "SR4") (pin "9") (pinfunction "QH'_9") (pintype "tri_state"))
      (node (ref "SR5") (pin "14") (pinfunction "SER_14") (pintype "input"))
    )
  )
)
